# PowerPlug.net
KiCad netlist of a schematic drawn in EAGLE
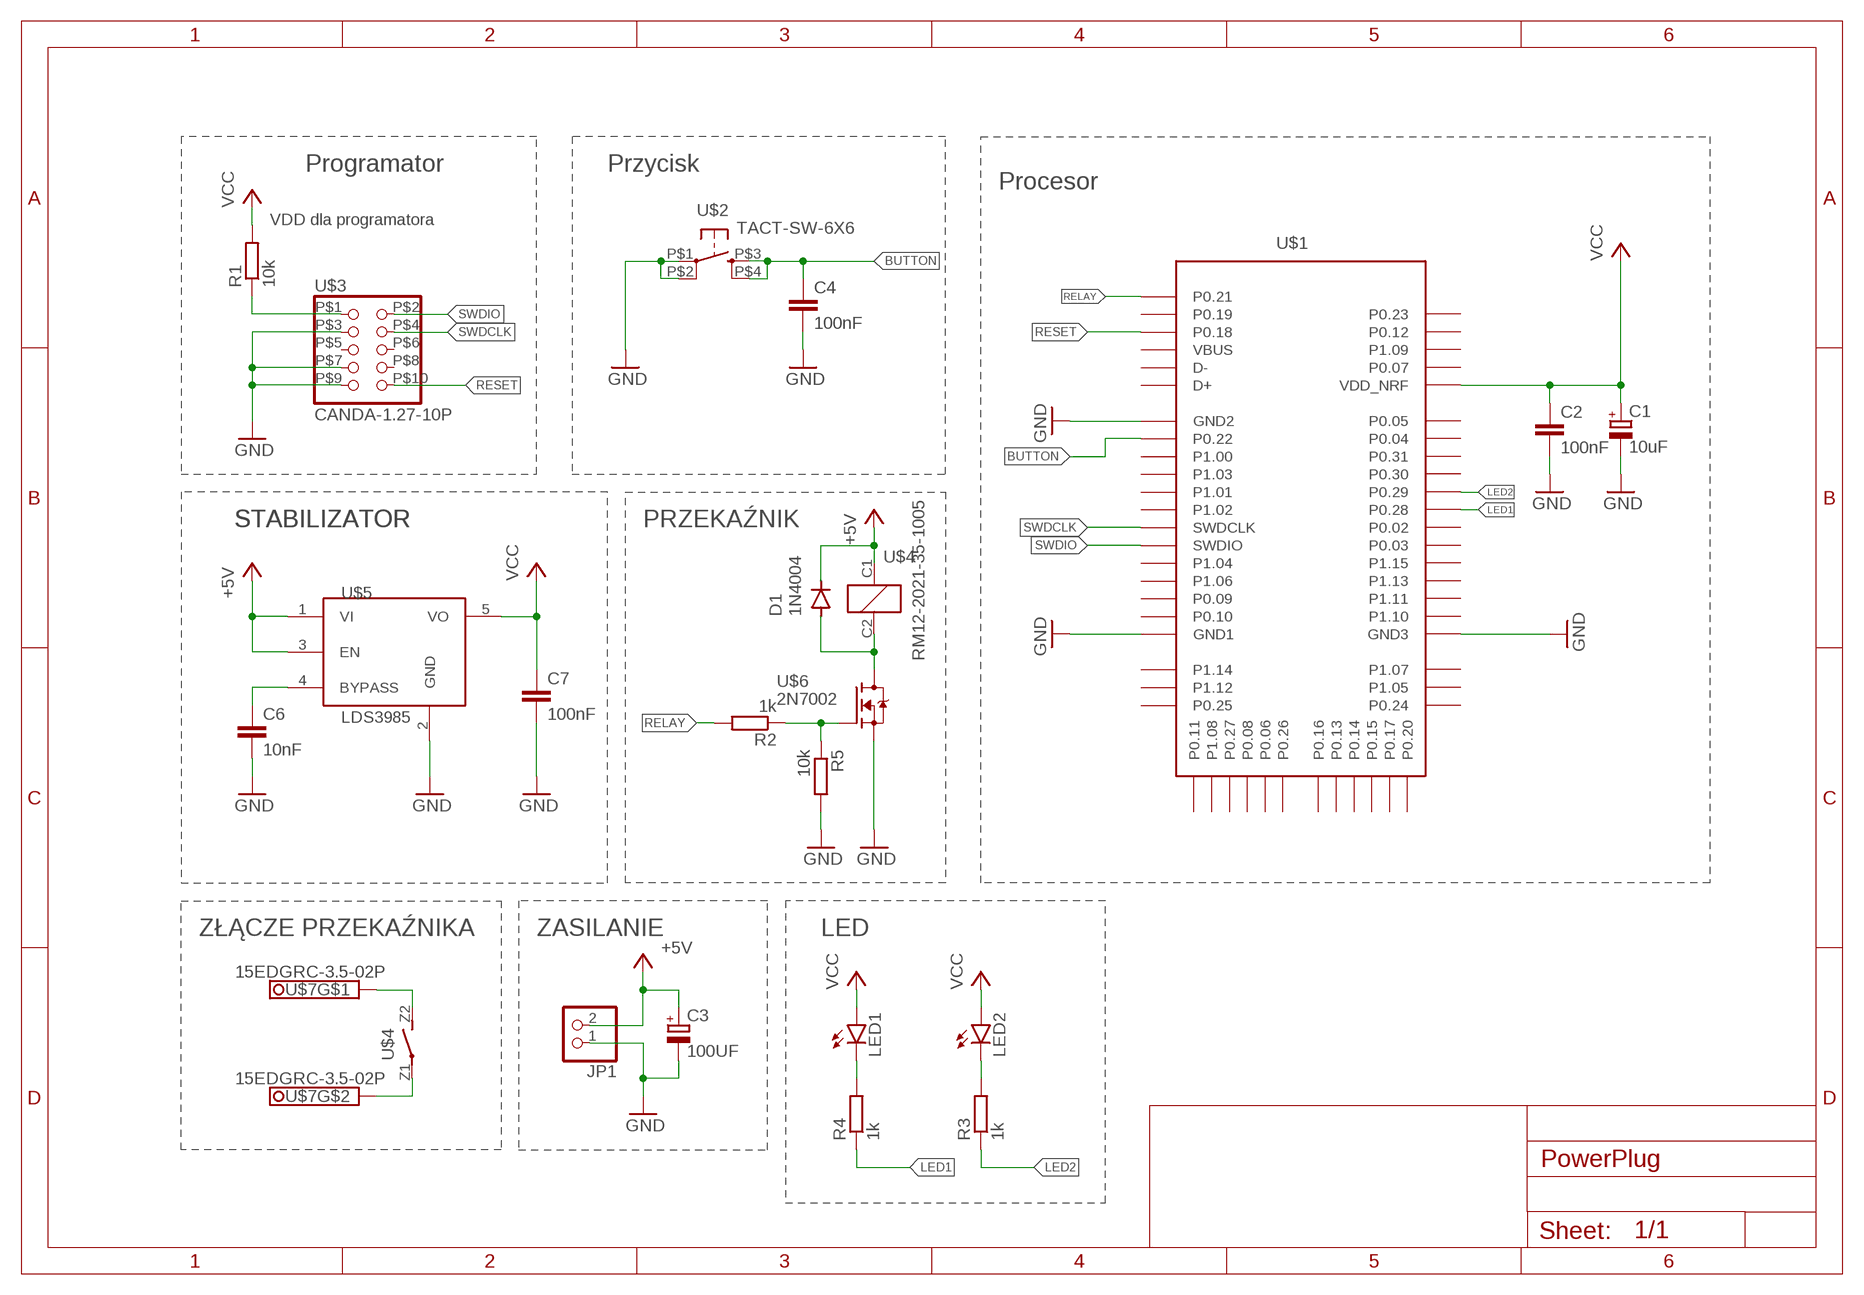
[diagram p0: schematic, sheet 1]

(export (version "E")
  (design (tool "Eeschema 10.0.6"))
  (components
    (comp (ref "C1")
      (value "10uF")
      (footprint "eagle-import:CT6032")
      (libsource (lib "eagle-import") (part "CPOL-EUCT6032"))
    )
    (comp (ref "C2")
      (value "100nF")
      (footprint "eagle-import:C0805K")
      (libsource (lib "eagle-import") (part "C-EUC0805K"))
    )
    (comp (ref "C3")
      (value "100UF")
      (footprint "eagle-import:153CLV-0605")
      (libsource (lib "eagle-import") (part "CPOL-EU153CLV-0605"))
    )
    (comp (ref "C4")
      (value "100nF")
      (footprint "eagle-import:C0805K")
      (libsource (lib "eagle-import") (part "C-EUC0805K"))
    )
    (comp (ref "C6")
      (value "10nF")
      (footprint "eagle-import:C0805K")
      (libsource (lib "eagle-import") (part "C-EUC0805K"))
    )
    (comp (ref "C7")
      (value "100nF")
      (footprint "eagle-import:C0805K")
      (libsource (lib "eagle-import") (part "C-EUC0805K"))
    )
    (comp (ref "D1")
      (value "1N4004")
      (footprint "eagle-import:DO41-10")
      (libsource (lib "eagle-import") (part "1N4004"))
    )
    (comp (ref "JP1")
      (value "PINHD-1X2")
      (footprint "eagle-import:1X02")
      (libsource (lib "eagle-import") (part "PINHD-1X2"))
    )
    (comp (ref "LED1")
      (value "LEDCHIPLED_0603")
      (footprint "eagle-import:CHIPLED_0603")
      (libsource (lib "eagle-import") (part "LEDCHIPLED_0603"))
    )
    (comp (ref "LED2")
      (value "LEDCHIPLED_0603")
      (footprint "eagle-import:CHIPLED_0603")
      (libsource (lib "eagle-import") (part "LEDCHIPLED_0603"))
    )
    (comp (ref "R1")
      (value "10k")
      (footprint "eagle-import:R0603")
      (libsource (lib "eagle-import") (part "R-EU_R0603"))
    )
    (comp (ref "R2")
      (value "1k")
      (footprint "eagle-import:R0603")
      (libsource (lib "eagle-import") (part "R-EU_R0603"))
    )
    (comp (ref "R3")
      (value "1k")
      (footprint "eagle-import:R0603")
      (libsource (lib "eagle-import") (part "R-EU_R0603"))
    )
    (comp (ref "R4")
      (value "1k")
      (footprint "eagle-import:R0603")
      (libsource (lib "eagle-import") (part "R-EU_R0603"))
    )
    (comp (ref "R5")
      (value "10k")
      (footprint "eagle-import:R0603")
      (libsource (lib "eagle-import") (part "R-EU_R0603"))
    )
    (comp (ref "U$1")
      (value "HOLYIOT_18010")
      (footprint "eagle-import:PCBCOMPONENT_1")
      (libsource (lib "eagle-import") (part "HOLYIOT_18010"))
    )
    (comp (ref "U$2")
      (value "TACT-SW-6X6")
      (footprint "eagle-import:6X6-TACT-SWITCH-SMD")
      (libsource (lib "eagle-import") (part "TACT-SW-6X6"))
    )
    (comp (ref "U$3")
      (value "CANDA-1.27-10P")
      (footprint "eagle-import:CON-1.27-CANDA")
      (libsource (lib "eagle-import") (part "CANDA-1.27-10P"))
    )
    (comp (ref "U$4")
      (value "RM12-2021-35-1005")
      (footprint "eagle-import:RM12-2021-35-1005")
      (libsource (lib "eagle-import") (part "RM12-2021-35-1005"))
    )
    (comp (ref "U$5")
      (value "LDS3985")
      (footprint "eagle-import:SOT23-5")
      (libsource (lib "eagle-import") (part "LDS3985"))
    )
    (comp (ref "U$6")
      (value "2N7002")
      (footprint "eagle-import:SOT23")
      (libsource (lib "eagle-import") (part "2N7002"))
    )
    (comp (ref "U$7")
      (value "15EDGRC-3.5-02P")
      (footprint "eagle-import:15EDGRC-3.5-02P")
      (libsource (lib "eagle-import") (part "15EDGRC-3.5-02P"))
    )
  )
  (nets
    (net (code "1") (name "+5V") (class "Default")
      (node (ref "C3") (pin "+") (pinfunction "+_+") (pintype "passive"))
      (node (ref "D1") (pin "C") (pinfunction "C_C") (pintype "passive"))
      (node (ref "JP1") (pin "2") (pinfunction "2_2") (pintype "passive"))
      (node (ref "U$4") (pin "C1") (pinfunction "1_C1") (pintype "passive"))
      (node (ref "U$5") (pin "1") (pinfunction "VI_1") (pintype "input"))
      (node (ref "U$5") (pin "3") (pinfunction "EN_3") (pintype "input"))
    )
    (net (code "2") (name "BUTTON") (class "Default")
      (node (ref "C4") (pin "1") (pinfunction "1_1") (pintype "passive"))
      (node (ref "U$1") (pin "P0.22") (pinfunction "P0.22_P0.22") (pintype "bidirectional"))
      (node (ref "U$2") (pin "P$3") (pinfunction "S_P$3") (pintype "passive"))
      (node (ref "U$2") (pin "P$4") (pinfunction "S1_P$4") (pintype "passive"))
    )
    (net (code "3") (name "GND") (class "Default")
      (node (ref "C1") (pin "-") (pinfunction "-_-") (pintype "passive"))
      (node (ref "C2") (pin "2") (pinfunction "2_2") (pintype "passive"))
      (node (ref "C3") (pin "-") (pinfunction "-_-") (pintype "passive"))
      (node (ref "C4") (pin "2") (pinfunction "2_2") (pintype "passive"))
      (node (ref "C6") (pin "2") (pinfunction "2_2") (pintype "passive"))
      (node (ref "C7") (pin "2") (pinfunction "2_2") (pintype "passive"))
      (node (ref "JP1") (pin "1") (pinfunction "1_1") (pintype "passive"))
      (node (ref "R5") (pin "2") (pinfunction "2_2") (pintype "passive"))
      (node (ref "U$1") (pin "GND") (pinfunction "GND1_GND") (pintype "bidirectional"))
      (node (ref "U$1") (pin "GND1") (pinfunction "GND2_GND1") (pintype "bidirectional"))
      (node (ref "U$1") (pin "GND2") (pinfunction "GND3_GND2") (pintype "bidirectional"))
      (node (ref "U$2") (pin "P$1") (pinfunction "P_P$1") (pintype "passive"))
      (node (ref "U$2") (pin "P$2") (pinfunction "P1_P$2") (pintype "passive"))
      (node (ref "U$3") (pin "P$3") (pinfunction "3_P$3") (pintype "passive"))
      (node (ref "U$3") (pin "P$7") (pinfunction "7_P$7") (pintype "passive"))
      (node (ref "U$3") (pin "P$9") (pinfunction "9_P$9") (pintype "passive"))
      (node (ref "U$5") (pin "2") (pinfunction "GND_2") (pintype "power_in"))
      (node (ref "U$6") (pin "2") (pinfunction "S_2") (pintype "passive"))
    )
    (net (code "4") (name "LED1") (class "Default")
      (node (ref "R4") (pin "1") (pinfunction "1_1") (pintype "passive"))
      (node (ref "U$1") (pin "P0.28") (pinfunction "P0.28_P0.28") (pintype "bidirectional"))
    )
    (net (code "5") (name "LED2") (class "Default")
      (node (ref "R3") (pin "1") (pinfunction "1_1") (pintype "passive"))
      (node (ref "U$1") (pin "P0.29") (pinfunction "P0.29_P0.29") (pintype "bidirectional"))
    )
    (net (code "6") (name "Net-(LED1-PadC)") (class "Default")
      (node (ref "LED1") (pin "C") (pinfunction "C_C") (pintype "passive"))
      (node (ref "R4") (pin "2") (pinfunction "2_2") (pintype "passive"))
    )
    (net (code "7") (name "Net-(LED2-PadC)") (class "Default")
      (node (ref "LED2") (pin "C") (pinfunction "C_C") (pintype "passive"))
      (node (ref "R3") (pin "2") (pinfunction "2_2") (pintype "passive"))
    )
    (net (code "8") (name "Net-(U$3-1)") (class "Default")
      (node (ref "R1") (pin "1") (pinfunction "1_1") (pintype "passive"))
      (node (ref "U$3") (pin "P$1") (pinfunction "1_P$1") (pintype "passive"))
    )
    (net (code "9") (name "Net-(U$4A-2)") (class "Default")
      (node (ref "D1") (pin "A") (pinfunction "A_A") (pintype "passive"))
      (node (ref "U$4") (pin "C2") (pinfunction "2_C2") (pintype "passive"))
      (node (ref "U$6") (pin "3") (pinfunction "D_3") (pintype "passive"))
    )
    (net (code "10") (name "Net-(U$4B-P)") (class "Default")
      (node (ref "U$4") (pin "Z1") (pinfunction "P_Z1") (pintype "passive"))
      (node (ref "U$7") (pin "P$2") (pinfunction "K_P$2") (pintype "passive"))
    )
    (net (code "11") (name "Net-(U$4B-S)") (class "Default")
      (node (ref "U$4") (pin "Z2") (pinfunction "S_Z2") (pintype "passive"))
      (node (ref "U$7") (pin "P$1") (pinfunction "K_P$1") (pintype "passive"))
    )
    (net (code "12") (name "Net-(U$5-BYPASS)") (class "Default")
      (node (ref "C6") (pin "1") (pinfunction "1_1") (pintype "passive"))
      (node (ref "U$5") (pin "4") (pinfunction "BYPASS_4") (pintype "bidirectional"))
    )
    (net (code "13") (name "Net-(U$6-G)") (class "Default")
      (node (ref "R2") (pin "1") (pinfunction "1_1") (pintype "passive"))
      (node (ref "R5") (pin "1") (pinfunction "1_1") (pintype "passive"))
      (node (ref "U$6") (pin "1") (pinfunction "G_1") (pintype "passive"))
    )
    (net (code "14") (name "RELAY") (class "Default")
      (node (ref "R2") (pin "2") (pinfunction "2_2") (pintype "passive"))
      (node (ref "U$1") (pin "P0.21") (pinfunction "P0.21_P0.21") (pintype "bidirectional"))
    )
    (net (code "15") (name "RESET") (class "Default")
      (node (ref "U$1") (pin "P0.18") (pinfunction "P0.18_P0.18") (pintype "bidirectional"))
      (node (ref "U$3") (pin "P$10") (pinfunction "10_P$10") (pintype "passive"))
    )
    (net (code "16") (name "SWDCLK") (class "Default")
      (node (ref "U$1") (pin "SWDCLK") (pinfunction "SWDCLK_SWDCLK") (pintype "bidirectional"))
      (node (ref "U$3") (pin "P$4") (pinfunction "4_P$4") (pintype "passive"))
    )
    (net (code "17") (name "SWDIO") (class "Default")
      (node (ref "U$1") (pin "SWDIO") (pinfunction "SWDIO_SWDIO") (pintype "bidirectional"))
      (node (ref "U$3") (pin "P$2") (pinfunction "2_P$2") (pintype "passive"))
    )
    (net (code "18") (name "VCC") (class "Default")
      (node (ref "C1") (pin "+") (pinfunction "+_+") (pintype "passive"))
      (node (ref "C2") (pin "1") (pinfunction "1_1") (pintype "passive"))
      (node (ref "C7") (pin "1") (pinfunction "1_1") (pintype "passive"))
      (node (ref "LED1") (pin "A") (pinfunction "A_A") (pintype "passive"))
      (node (ref "LED2") (pin "A") (pinfunction "A_A") (pintype "passive"))
      (node (ref "R1") (pin "2") (pinfunction "2_2") (pintype "passive"))
      (node (ref "U$1") (pin "VDD_NRF") (pinfunction "VDD_NRF_VDD_NRF") (pintype "bidirectional"))
      (node (ref "U$5") (pin "5") (pinfunction "VO_5") (pintype "power_in"))
    )
    (net (code "19") (name "unconnected-(U$1-PadD+)") (class "Default")
      (node (ref "U$1") (pin "D+") (pinfunction "D+_D+") (pintype "bidirectional"))
    )
    (net (code "20") (name "unconnected-(U$1-PadD-)") (class "Default")
      (node (ref "U$1") (pin "D-") (pinfunction "D-_D-") (pintype "bidirectional"))
    )
    (net (code "21") (name "unconnected-(U$1-PadP0.02)") (class "Default")
      (node (ref "U$1") (pin "P0.02") (pinfunction "P0.02_P0.02") (pintype "bidirectional"))
    )
    (net (code "22") (name "unconnected-(U$1-PadP0.03)") (class "Default")
      (node (ref "U$1") (pin "P0.03") (pinfunction "P0.03_P0.03") (pintype "bidirectional"))
    )
    (net (code "23") (name "unconnected-(U$1-PadP0.04)") (class "Default")
      (node (ref "U$1") (pin "P0.04") (pinfunction "P0.04_P0.04") (pintype "bidirectional"))
    )
    (net (code "24") (name "unconnected-(U$1-PadP0.05)") (class "Default")
      (node (ref "U$1") (pin "P0.05") (pinfunction "P0.05_P0.05") (pintype "bidirectional"))
    )
    (net (code "25") (name "unconnected-(U$1-PadP0.06)") (class "Default")
      (node (ref "U$1") (pin "P0.06") (pinfunction "P0.06_P0.06") (pintype "bidirectional"))
    )
    (net (code "26") (name "unconnected-(U$1-PadP0.07)") (class "Default")
      (node (ref "U$1") (pin "P0.07") (pinfunction "P0.07_P0.07") (pintype "bidirectional"))
    )
    (net (code "27") (name "unconnected-(U$1-PadP0.08)") (class "Default")
      (node (ref "U$1") (pin "P0.08") (pinfunction "P0.08_P0.08") (pintype "bidirectional"))
    )
    (net (code "28") (name "unconnected-(U$1-PadP0.09)") (class "Default")
      (node (ref "U$1") (pin "P0.09") (pinfunction "P0.09_P0.09") (pintype "bidirectional"))
    )
    (net (code "29") (name "unconnected-(U$1-PadP0.10)") (class "Default")
      (node (ref "U$1") (pin "P0.10") (pinfunction "P0.10_P0.10") (pintype "bidirectional"))
    )
    (net (code "30") (name "unconnected-(U$1-PadP0.11)") (class "Default")
      (node (ref "U$1") (pin "P0.11") (pinfunction "P0.11_P0.11") (pintype "bidirectional"))
    )
    (net (code "31") (name "unconnected-(U$1-PadP0.12)") (class "Default")
      (node (ref "U$1") (pin "P0.12") (pinfunction "P0.12_P0.12") (pintype "bidirectional"))
    )
    (net (code "32") (name "unconnected-(U$1-PadP0.13)") (class "Default")
      (node (ref "U$1") (pin "P0.13") (pinfunction "P0.13_P0.13") (pintype "bidirectional"))
    )
    (net (code "33") (name "unconnected-(U$1-PadP0.14)") (class "Default")
      (node (ref "U$1") (pin "P0.14") (pinfunction "P0.14_P0.14") (pintype "bidirectional"))
    )
    (net (code "34") (name "unconnected-(U$1-PadP0.15)") (class "Default")
      (node (ref "U$1") (pin "P0.15") (pinfunction "P0.15_P0.15") (pintype "bidirectional"))
    )
    (net (code "35") (name "unconnected-(U$1-PadP0.16)") (class "Default")
      (node (ref "U$1") (pin "P0.16") (pinfunction "P0.16_P0.16") (pintype "bidirectional"))
    )
    (net (code "36") (name "unconnected-(U$1-PadP0.17)") (class "Default")
      (node (ref "U$1") (pin "P0.17") (pinfunction "P0.17_P0.17") (pintype "bidirectional"))
    )
    (net (code "37") (name "unconnected-(U$1-PadP0.19)") (class "Default")
      (node (ref "U$1") (pin "P0.19") (pinfunction "P0.19_P0.19") (pintype "bidirectional"))
    )
    (net (code "38") (name "unconnected-(U$1-PadP0.20)") (class "Default")
      (node (ref "U$1") (pin "P0.20") (pinfunction "P0.20_P0.20") (pintype "bidirectional"))
    )
    (net (code "39") (name "unconnected-(U$1-PadP0.23)") (class "Default")
      (node (ref "U$1") (pin "P0.23") (pinfunction "P0.23_P0.23") (pintype "bidirectional"))
    )
    (net (code "40") (name "unconnected-(U$1-PadP0.24)") (class "Default")
      (node (ref "U$1") (pin "P0.24") (pinfunction "P0.24_P0.24") (pintype "bidirectional"))
    )
    (net (code "41") (name "unconnected-(U$1-PadP0.25)") (class "Default")
      (node (ref "U$1") (pin "P0.25") (pinfunction "P0.25_P0.25") (pintype "bidirectional"))
    )
    (net (code "42") (name "unconnected-(U$1-PadP0.26)") (class "Default")
      (node (ref "U$1") (pin "P0.26") (pinfunction "P0.26_P0.26") (pintype "bidirectional"))
    )
    (net (code "43") (name "unconnected-(U$1-PadP0.27)") (class "Default")
      (node (ref "U$1") (pin "P0.27") (pinfunction "P0.27_P0.27") (pintype "bidirectional"))
    )
    (net (code "44") (name "unconnected-(U$1-PadP0.30)") (class "Default")
      (node (ref "U$1") (pin "P0.30") (pinfunction "P0.30_P0.30") (pintype "bidirectional"))
    )
    (net (code "45") (name "unconnected-(U$1-PadP0.31)") (class "Default")
      (node (ref "U$1") (pin "P0.31") (pinfunction "P0.31_P0.31") (pintype "bidirectional"))
    )
    (net (code "46") (name "unconnected-(U$1-PadP1.00)") (class "Default")
      (node (ref "U$1") (pin "P1.00") (pinfunction "P1.00_P1.00") (pintype "bidirectional"))
    )
    (net (code "47") (name "unconnected-(U$1-PadP1.01)") (class "Default")
      (node (ref "U$1") (pin "P1.01") (pinfunction "P1.01_P1.01") (pintype "bidirectional"))
    )
    (net (code "48") (name "unconnected-(U$1-PadP1.02)") (class "Default")
      (node (ref "U$1") (pin "P1.02") (pinfunction "P1.02_P1.02") (pintype "bidirectional"))
    )
    (net (code "49") (name "unconnected-(U$1-PadP1.03)") (class "Default")
      (node (ref "U$1") (pin "P1.03") (pinfunction "P1.03_P1.03") (pintype "bidirectional"))
    )
    (net (code "50") (name "unconnected-(U$1-PadP1.04)") (class "Default")
      (node (ref "U$1") (pin "P1.04") (pinfunction "P1.04_P1.04") (pintype "bidirectional"))
    )
    (net (code "51") (name "unconnected-(U$1-PadP1.05)") (class "Default")
      (node (ref "U$1") (pin "P1.05") (pinfunction "P1.05_P1.05") (pintype "bidirectional"))
    )
    (net (code "52") (name "unconnected-(U$1-PadP1.06)") (class "Default")
      (node (ref "U$1") (pin "P1.06") (pinfunction "P1.06_P1.06") (pintype "bidirectional"))
    )
    (net (code "53") (name "unconnected-(U$1-PadP1.07)") (class "Default")
      (node (ref "U$1") (pin "P1.07") (pinfunction "P1.07_P1.07") (pintype "bidirectional"))
    )
    (net (code "54") (name "unconnected-(U$1-PadP1.08)") (class "Default")
      (node (ref "U$1") (pin "P1.08") (pinfunction "P1.08_P1.08") (pintype "bidirectional"))
    )
    (net (code "55") (name "unconnected-(U$1-PadP1.09)") (class "Default")
      (node (ref "U$1") (pin "P1.09") (pinfunction "P1.09_P1.09") (pintype "bidirectional"))
    )
    (net (code "56") (name "unconnected-(U$1-PadP1.10)") (class "Default")
      (node (ref "U$1") (pin "P1.10") (pinfunction "P1.10_P1.10") (pintype "bidirectional"))
    )
    (net (code "57") (name "unconnected-(U$1-PadP1.11)") (class "Default")
      (node (ref "U$1") (pin "P1.11") (pinfunction "P1.11_P1.11") (pintype "bidirectional"))
    )
    (net (code "58") (name "unconnected-(U$1-PadP1.12)") (class "Default")
      (node (ref "U$1") (pin "P1.12") (pinfunction "P1.12_P1.12") (pintype "bidirectional"))
    )
    (net (code "59") (name "unconnected-(U$1-PadP1.13)") (class "Default")
      (node (ref "U$1") (pin "P1.13") (pinfunction "P1.13_P1.13") (pintype "bidirectional"))
    )
    (net (code "60") (name "unconnected-(U$1-PadP1.14)") (class "Default")
      (node (ref "U$1") (pin "P1.14") (pinfunction "P1.14_P1.14") (pintype "bidirectional"))
    )
    (net (code "61") (name "unconnected-(U$1-PadP1.15)") (class "Default")
      (node (ref "U$1") (pin "P1.15") (pinfunction "P1.15_P1.15") (pintype "bidirectional"))
    )
    (net (code "62") (name "unconnected-(U$1-PadVBUS)") (class "Default")
      (node (ref "U$1") (pin "VBUS") (pinfunction "VBUS_VBUS") (pintype "bidirectional"))
    )
    (net (code "63") (name "unconnected-(U$3-5-PadP$5)") (class "Default")
      (node (ref "U$3") (pin "P$5") (pinfunction "5_P$5") (pintype "passive"))
    )
    (net (code "64") (name "unconnected-(U$3-6-PadP$6)") (class "Default")
      (node (ref "U$3") (pin "P$6") (pinfunction "6_P$6") (pintype "passive"))
    )
    (net (code "65") (name "unconnected-(U$3-8-PadP$8)") (class "Default")
      (node (ref "U$3") (pin "P$8") (pinfunction "8_P$8") (pintype "passive"))
    )
  )
)
